# schematic.net
KiCad netlist of a schematic drawn in EasyEDA
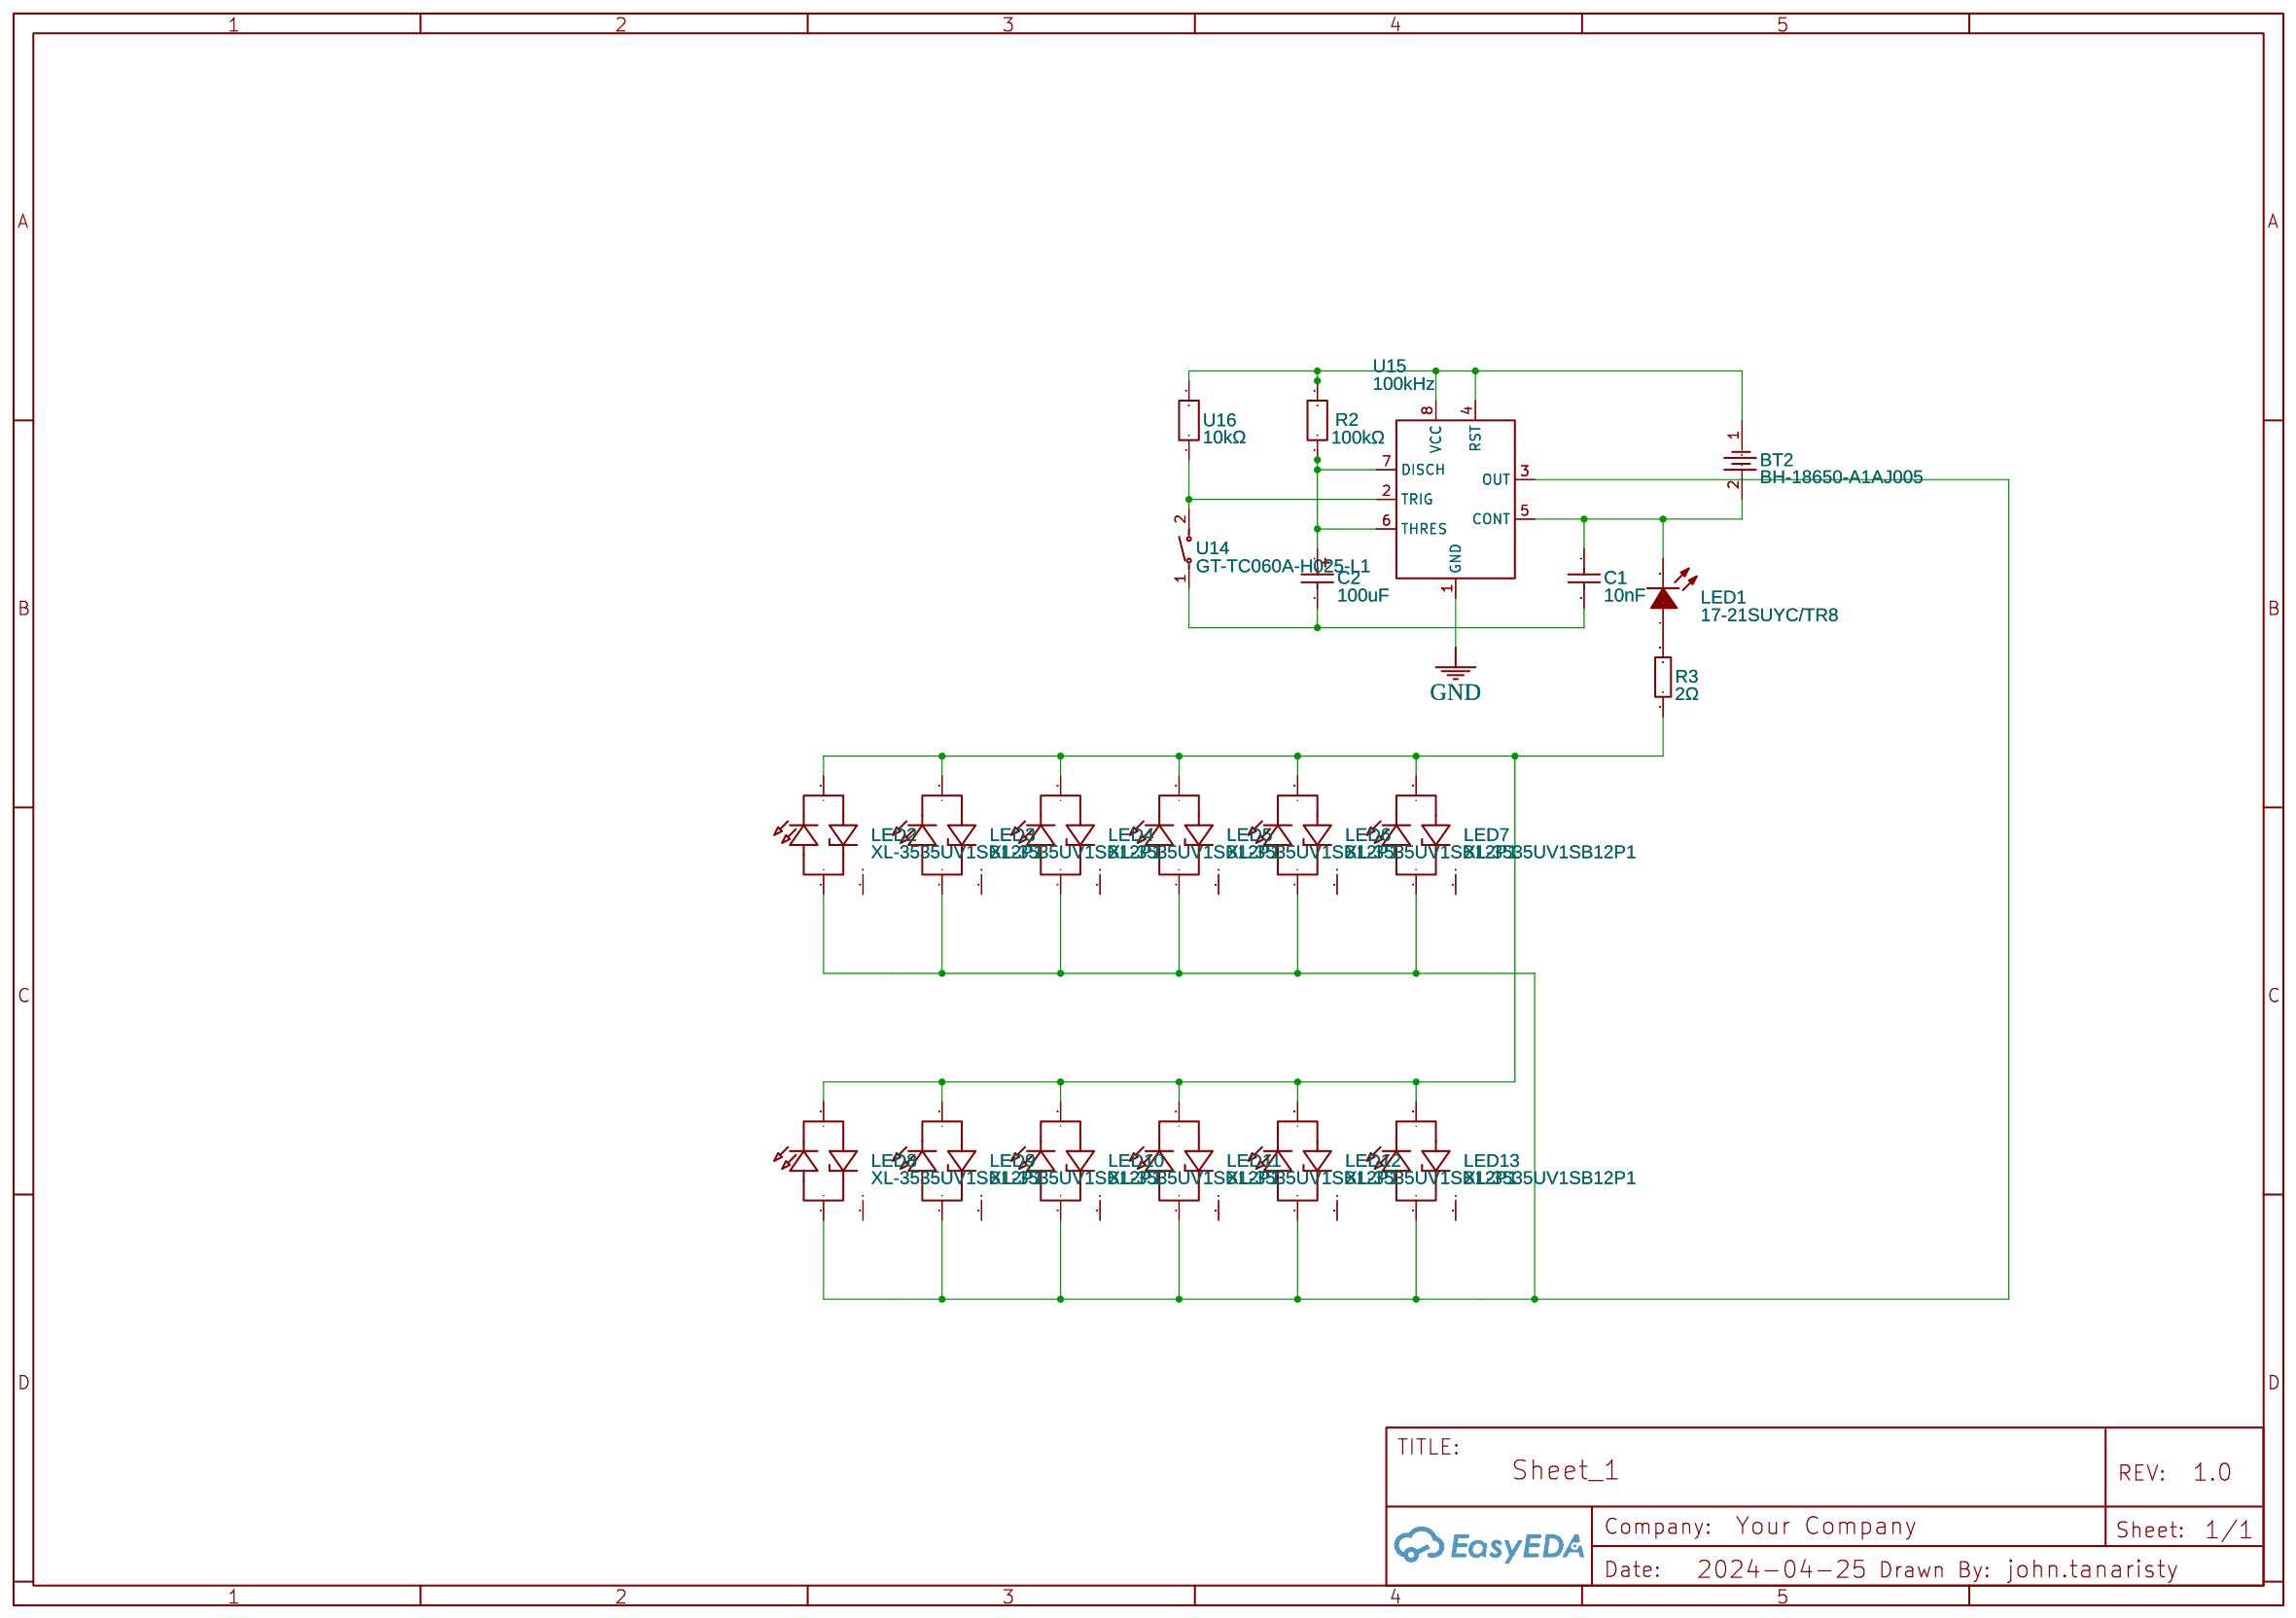
[diagram p0: schematic sheet]

(export (version "E")
  (design (tool "Eeschema 10.0.6"))
  (components
    (comp (ref "BT2")
      (value "BH-18650-A1AJ005")
      (fields (field (name "Manufacturer") "MYOUNG(美阳)"))
      (libsource (lib "") (part "BH-18650-A1AJ005"))
    )
    (comp (ref "C1")
      (value "10nF")
      (fields
        (field (name "Manufacturer Part") "CC0402KRX7R9BB103")
        (field (name "Manufacturer") "YAGEO(国巨)")
      )
      (libsource (lib "") (part "CC0402KRX7R9BB103"))
    )
    (comp (ref "C2")
      (value "100uF")
      (fields
        (field (name "Manufacturer Part") "TLJA107M006R0800")
        (field (name "Manufacturer") "Kyocera AVX")
      )
      (libsource (lib "") (part "TLJA107M006R0800"))
    )
    (comp (ref "LED1")
      (value "17-21SUYC/TR8")
      (fields (field (name "Manufacturer Part") "KT-0805黄灯") (field (name "Manufacturer") "KENTO"))
      (libsource (lib "") (part "17-21SUYC/TR8"))
    )
    (comp (ref "LED2")
      (value "XL-3535UV1SB12P1")
      (fields (field (name "Manufacturer") "XINGLIGHT(成兴光)"))
      (libsource (lib "") (part "XL-3535UV1SB12P1"))
    )
    (comp (ref "LED3")
      (value "XL-3535UV1SB12P1")
      (fields (field (name "Manufacturer") "XINGLIGHT(成兴光)"))
      (libsource (lib "") (part "XL-3535UV1SB12P1"))
    )
    (comp (ref "LED4")
      (value "XL-3535UV1SB12P1")
      (fields (field (name "Manufacturer") "XINGLIGHT(成兴光)"))
      (libsource (lib "") (part "XL-3535UV1SB12P1"))
    )
    (comp (ref "LED5")
      (value "XL-3535UV1SB12P1")
      (fields (field (name "Manufacturer") "XINGLIGHT(成兴光)"))
      (libsource (lib "") (part "XL-3535UV1SB12P1"))
    )
    (comp (ref "LED6")
      (value "XL-3535UV1SB12P1")
      (fields (field (name "Manufacturer") "XINGLIGHT(成兴光)"))
      (libsource (lib "") (part "XL-3535UV1SB12P1"))
    )
    (comp (ref "LED7")
      (value "XL-3535UV1SB12P1")
      (fields (field (name "Manufacturer") "XINGLIGHT(成兴光)"))
      (libsource (lib "") (part "XL-3535UV1SB12P1"))
    )
    (comp (ref "LED8")
      (value "XL-3535UV1SB12P1")
      (fields (field (name "Manufacturer") "XINGLIGHT(成兴光)"))
      (libsource (lib "") (part "XL-3535UV1SB12P1"))
    )
    (comp (ref "LED9")
      (value "XL-3535UV1SB12P1")
      (fields (field (name "Manufacturer") "XINGLIGHT(成兴光)"))
      (libsource (lib "") (part "XL-3535UV1SB12P1"))
    )
    (comp (ref "LED10")
      (value "XL-3535UV1SB12P1")
      (fields (field (name "Manufacturer") "XINGLIGHT(成兴光)"))
      (libsource (lib "") (part "XL-3535UV1SB12P1"))
    )
    (comp (ref "LED11")
      (value "XL-3535UV1SB12P1")
      (fields (field (name "Manufacturer") "XINGLIGHT(成兴光)"))
      (libsource (lib "") (part "XL-3535UV1SB12P1"))
    )
    (comp (ref "LED12")
      (value "XL-3535UV1SB12P1")
      (fields (field (name "Manufacturer") "XINGLIGHT(成兴光)"))
      (libsource (lib "") (part "XL-3535UV1SB12P1"))
    )
    (comp (ref "LED13")
      (value "XL-3535UV1SB12P1")
      (fields (field (name "Manufacturer") "XINGLIGHT(成兴光)"))
      (libsource (lib "") (part "XL-3535UV1SB12P1"))
    )
    (comp (ref "R2")
      (value "100kΩ")
      (fields (field (name "Manufacturer Part") "FRC0805J104 TS") (field (name "Manufacturer") "FOJAN(富捷)"))
      (libsource (lib "") (part "FRC0805J104 TS"))
    )
    (comp (ref "R3")
      (value "2Ω")
      (fields
        (field (name "Manufacturer Part") "0603WAF200KT5E")
        (field (name "Manufacturer") "UNI-ROYAL(厚声)")
      )
      (libsource (lib "") (part "0603WAF200KT5E"))
    )
    (comp (ref "U14")
      (value "GT-TC060A-H025-L1")
      (fields (field (name "Manufacturer") "G-Switch(品赞)"))
      (libsource (lib "") (part "GT-TC060A-H025-L1"))
    )
    (comp (ref "U15")
      (value "100kHz")
      (fields (field (name "Manufacturer Part") "NE555DR") (field (name "Manufacturer") "TI(德州仪器)"))
      (libsource (lib "") (part "NE555DR"))
    )
    (comp (ref "U16")
      (value "10kΩ")
      (fields (field (name "Manufacturer Part") "ABD03K1002FT") (field (name "Manufacturer") "FH(风华)"))
      (libsource (lib "") (part "ABD03K1002FT"))
    )
  )
  (nets
    (net (code "1") (name "GND") (class "Default")
      (node (ref "U15") (pin "1") (pinfunction "GND_1") (pintype "unspecified"))
    )
    (net (code "2") (name "Net-(C1-Pad2)") (class "Default")
      (node (ref "C1") (pin "2") (pinfunction "2_2") (pintype "input"))
      (node (ref "C2") (pin "2") (pinfunction "2_2") (pintype "input"))
      (node (ref "U14") (pin "1") (pinfunction "1_1") (pintype "unspecified"))
    )
    (net (code "3") (name "Net-(LED1-+)") (class "Default")
      (node (ref "LED1") (pin "1") (pinfunction "+_1") (pintype "unspecified"))
      (node (ref "R3") (pin "2") (pinfunction "2_2") (pintype "input"))
    )
    (net (code "4") (name "Net-(LED1--)") (class "Default")
      (node (ref "BT2") (pin "2") (pinfunction "2_2") (pintype "input"))
      (node (ref "C1") (pin "1") (pinfunction "1_1") (pintype "input"))
      (node (ref "LED1") (pin "2") (pinfunction "-_2") (pintype "unspecified"))
      (node (ref "U15") (pin "5") (pinfunction "CONT_5") (pintype "unspecified"))
    )
    (net (code "5") (name "Net-(LED10-+)") (class "Default")
      (node (ref "LED10") (pin "1") (pinfunction "+_1") (pintype "unspecified"))
      (node (ref "LED11") (pin "1") (pinfunction "+_1") (pintype "unspecified"))
      (node (ref "LED12") (pin "1") (pinfunction "+_1") (pintype "unspecified"))
      (node (ref "LED13") (pin "1") (pinfunction "+_1") (pintype "unspecified"))
      (node (ref "LED2") (pin "1") (pinfunction "+_1") (pintype "unspecified"))
      (node (ref "LED3") (pin "1") (pinfunction "+_1") (pintype "unspecified"))
      (node (ref "LED4") (pin "1") (pinfunction "+_1") (pintype "unspecified"))
      (node (ref "LED5") (pin "1") (pinfunction "+_1") (pintype "unspecified"))
      (node (ref "LED6") (pin "1") (pinfunction "+_1") (pintype "unspecified"))
      (node (ref "LED7") (pin "1") (pinfunction "+_1") (pintype "unspecified"))
      (node (ref "LED8") (pin "1") (pinfunction "+_1") (pintype "unspecified"))
      (node (ref "LED9") (pin "1") (pinfunction "+_1") (pintype "unspecified"))
      (node (ref "U15") (pin "3") (pinfunction "OUT_3") (pintype "unspecified"))
    )
    (net (code "6") (name "Net-(LED10--)") (class "Default")
      (node (ref "LED10") (pin "2") (pinfunction "-_2") (pintype "unspecified"))
      (node (ref "LED11") (pin "2") (pinfunction "-_2") (pintype "unspecified"))
      (node (ref "LED12") (pin "2") (pinfunction "-_2") (pintype "unspecified"))
      (node (ref "LED13") (pin "2") (pinfunction "-_2") (pintype "unspecified"))
      (node (ref "LED2") (pin "2") (pinfunction "-_2") (pintype "unspecified"))
      (node (ref "LED3") (pin "2") (pinfunction "-_2") (pintype "unspecified"))
      (node (ref "LED4") (pin "2") (pinfunction "-_2") (pintype "unspecified"))
      (node (ref "LED5") (pin "2") (pinfunction "-_2") (pintype "unspecified"))
      (node (ref "LED6") (pin "2") (pinfunction "-_2") (pintype "unspecified"))
      (node (ref "LED7") (pin "2") (pinfunction "-_2") (pintype "unspecified"))
      (node (ref "LED8") (pin "2") (pinfunction "-_2") (pintype "unspecified"))
      (node (ref "LED9") (pin "2") (pinfunction "-_2") (pintype "unspecified"))
      (node (ref "R3") (pin "1") (pinfunction "1_1") (pintype "input"))
    )
    (net (code "7") (name "Net-(U15-DISCH)") (class "Default")
      (node (ref "C2") (pin "1") (pinfunction "1_1") (pintype "input"))
      (node (ref "R2") (pin "1") (pinfunction "1_1") (pintype "unspecified"))
      (node (ref "U15") (pin "6") (pinfunction "THRES_6") (pintype "unspecified"))
      (node (ref "U15") (pin "7") (pinfunction "DISCH_7") (pintype "unspecified"))
    )
    (net (code "8") (name "Net-(U15-RST)") (class "Default")
      (node (ref "BT2") (pin "1") (pinfunction "1_1") (pintype "input"))
      (node (ref "R2") (pin "2") (pinfunction "2_2") (pintype "unspecified"))
      (node (ref "U15") (pin "4") (pinfunction "RST_4") (pintype "unspecified"))
      (node (ref "U15") (pin "8") (pinfunction "VCC_8") (pintype "unspecified"))
      (node (ref "U16") (pin "2") (pinfunction "2_2") (pintype "unspecified"))
    )
    (net (code "9") (name "Net-(U15-TRIG)") (class "Default")
      (node (ref "U14") (pin "2") (pinfunction "2_2") (pintype "unspecified"))
      (node (ref "U15") (pin "2") (pinfunction "TRIG_2") (pintype "unspecified"))
      (node (ref "U16") (pin "1") (pinfunction "1_1") (pintype "unspecified"))
    )
    (net (code "10") (name "unconnected-(LED2-Pad3)") (class "Default")
      (node (ref "LED2") (pin "3") (pinfunction "3_3") (pintype "unspecified"))
    )
    (net (code "11") (name "unconnected-(LED3-Pad3)") (class "Default")
      (node (ref "LED3") (pin "3") (pinfunction "3_3") (pintype "unspecified"))
    )
    (net (code "12") (name "unconnected-(LED4-Pad3)") (class "Default")
      (node (ref "LED4") (pin "3") (pinfunction "3_3") (pintype "unspecified"))
    )
    (net (code "13") (name "unconnected-(LED5-Pad3)") (class "Default")
      (node (ref "LED5") (pin "3") (pinfunction "3_3") (pintype "unspecified"))
    )
    (net (code "14") (name "unconnected-(LED6-Pad3)") (class "Default")
      (node (ref "LED6") (pin "3") (pinfunction "3_3") (pintype "unspecified"))
    )
    (net (code "15") (name "unconnected-(LED7-Pad3)") (class "Default")
      (node (ref "LED7") (pin "3") (pinfunction "3_3") (pintype "unspecified"))
    )
    (net (code "16") (name "unconnected-(LED8-Pad3)") (class "Default")
      (node (ref "LED8") (pin "3") (pinfunction "3_3") (pintype "unspecified"))
    )
    (net (code "17") (name "unconnected-(LED9-Pad3)") (class "Default")
      (node (ref "LED9") (pin "3") (pinfunction "3_3") (pintype "unspecified"))
    )
    (net (code "18") (name "unconnected-(LED10-Pad3)") (class "Default")
      (node (ref "LED10") (pin "3") (pinfunction "3_3") (pintype "unspecified"))
    )
    (net (code "19") (name "unconnected-(LED11-Pad3)") (class "Default")
      (node (ref "LED11") (pin "3") (pinfunction "3_3") (pintype "unspecified"))
    )
    (net (code "20") (name "unconnected-(LED12-Pad3)") (class "Default")
      (node (ref "LED12") (pin "3") (pinfunction "3_3") (pintype "unspecified"))
    )
    (net (code "21") (name "unconnected-(LED13-Pad3)") (class "Default")
      (node (ref "LED13") (pin "3") (pinfunction "3_3") (pintype "unspecified"))
    )
  )
)
